# FTDI_only.net
KiCad netlist of a schematic drawn in EAGLE
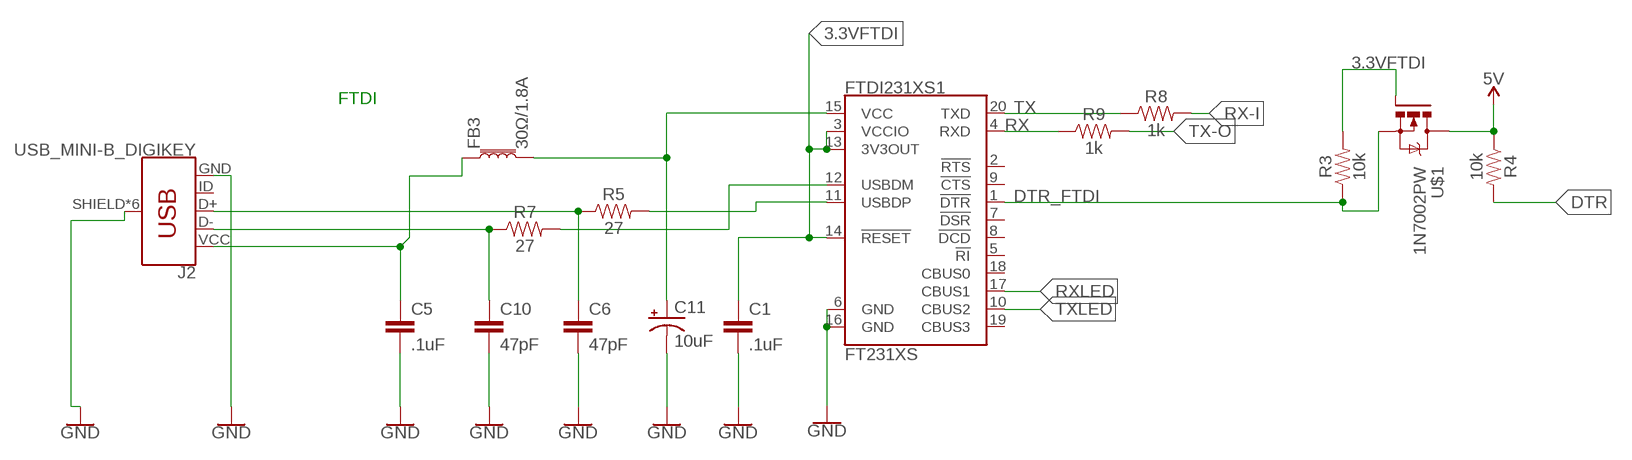
[diagram p0: schematic, sheet 1]

(export (version "E")
  (design (tool "Eeschema 10.0.6"))
  (components
    (comp (ref "C1")
      (value ".1uF")
      (footprint "eagle-import:0402-CAP")
      (libsource (lib "eagle-import") (part ".22UF-CER"))
    )
    (comp (ref "C5")
      (value ".1uF")
      (footprint "eagle-import:0402-CAP")
      (libsource (lib "eagle-import") (part ".22UF-CER"))
    )
    (comp (ref "C6")
      (value "47pF")
      (footprint "eagle-import:0402-CAP")
      (libsource (lib "eagle-import") (part ".22UF-CER"))
    )
    (comp (ref "C10")
      (value "47pF")
      (footprint "eagle-import:0402-CAP")
      (libsource (lib "eagle-import") (part ".22UF-CER"))
    )
    (comp (ref "C11")
      (value "10uF")
      (footprint "eagle-import:EIA3216")
      (libsource (lib "eagle-import") (part "10UF-TANT"))
    )
    (comp (ref "FB3")
      (value "30Ω/1.8A")
      (footprint "eagle-import:0603")
      (libsource (lib "eagle-import") (part "FERRITE_BEAD-0603"))
    )
    (comp (ref "FTDI231XS1")
      (value "FT231XS")
      (footprint "eagle-import:SSOP20_L")
      (libsource (lib "eagle-import") (part "FT231XS"))
    )
    (comp (ref "J2")
      (value "USB_MINI-B_DIGIKEY")
      (footprint "eagle-import:MICRO-USB-DIGIKEY-FCI2")
      (libsource (lib "eagle-import") (part "USB_MINI-B_DIGIKEY"))
    )
    (comp (ref "R3")
      (value "10k")
      (footprint "eagle-import:0603")
      (libsource (lib "eagle-import") (part "0.05OHM-0603-1/5W-1%"))
    )
    (comp (ref "R4")
      (value "10k")
      (footprint "eagle-import:0603")
      (libsource (lib "eagle-import") (part "0.05OHM-0603-1/5W-1%"))
    )
    (comp (ref "R5")
      (value "27")
      (footprint "eagle-import:0603")
      (libsource (lib "eagle-import") (part "0.05OHM-0603-1/5W-1%"))
    )
    (comp (ref "R7")
      (value "27")
      (footprint "eagle-import:0603")
      (libsource (lib "eagle-import") (part "0.05OHM-0603-1/5W-1%"))
    )
    (comp (ref "R8")
      (value "1k")
      (footprint "eagle-import:0603")
      (libsource (lib "eagle-import") (part "0.05OHM-0603-1/5W-1%"))
    )
    (comp (ref "R9")
      (value "1k")
      (footprint "eagle-import:0603")
      (libsource (lib "eagle-import") (part "0.05OHM-0603-1/5W-1%"))
    )
    (comp (ref "U$1")
      (value "1N7002PW")
      (footprint "eagle-import:SOT323W_INFINEON")
      (libsource (lib "eagle-import") (part "1N7002PW"))
    )
  )
  (nets
    (net (code "1") (name "/DTR_FTDI") (class "Default")
      (node (ref "FTDI231XS1") (pin "1") (pinfunction "~{DTR}_1") (pintype "bidirectional"))
      (node (ref "R3") (pin "1") (pinfunction "1_1") (pintype "passive"))
      (node (ref "U$1") (pin "2") (pinfunction "S_2") (pintype "passive"))
    )
    (net (code "2") (name "/RX") (class "Default")
      (node (ref "FTDI231XS1") (pin "4") (pinfunction "RXD_4") (pintype "bidirectional"))
      (node (ref "R9") (pin "1") (pinfunction "1_1") (pintype "passive"))
    )
    (net (code "3") (name "/TX") (class "Default")
      (node (ref "FTDI231XS1") (pin "20") (pinfunction "TXD_20") (pintype "bidirectional"))
      (node (ref "R8") (pin "1") (pinfunction "1_1") (pintype "passive"))
    )
    (net (code "4") (name "/VUSB") (class "Default")
      (node (ref "C11") (pin "A") (pinfunction "+_A") (pintype "passive"))
      (node (ref "C5") (pin "1") (pinfunction "1_1") (pintype "passive"))
      (node (ref "FB3") (pin "1") (pinfunction "1_1") (pintype "passive"))
      (node (ref "FB3") (pin "2") (pinfunction "2_2") (pintype "passive"))
      (node (ref "FTDI231XS1") (pin "15") (pinfunction "VCC_15") (pintype "bidirectional"))
      (node (ref "J2") (pin "VCC") (pinfunction "VBUS_VCC") (pintype "power_in"))
    )
    (net (code "5") (name "3.3VFTDI") (class "Default")
      (node (ref "C1") (pin "1") (pinfunction "1_1") (pintype "passive"))
      (node (ref "FTDI231XS1") (pin "13") (pinfunction "3V3OUT_13") (pintype "bidirectional"))
      (node (ref "FTDI231XS1") (pin "14") (pinfunction "~{RESET}_14") (pintype "bidirectional"))
      (node (ref "FTDI231XS1") (pin "3") (pinfunction "VCCIO_3") (pintype "bidirectional"))
      (node (ref "R3") (pin "2") (pinfunction "2_2") (pintype "passive"))
      (node (ref "U$1") (pin "1") (pinfunction "G_1") (pintype "passive"))
    )
    (net (code "6") (name "5V") (class "Default")
      (node (ref "R4") (pin "1") (pinfunction "1_1") (pintype "passive"))
      (node (ref "U$1") (pin "3") (pinfunction "D_3") (pintype "passive"))
    )
    (net (code "7") (name "DTR") (class "Default")
      (node (ref "R4") (pin "2") (pinfunction "2_2") (pintype "passive"))
    )
    (net (code "8") (name "GND") (class "Default")
      (node (ref "C1") (pin "2") (pinfunction "2_2") (pintype "passive"))
      (node (ref "C10") (pin "2") (pinfunction "2_2") (pintype "passive"))
      (node (ref "C11") (pin "C") (pinfunction "-_C") (pintype "passive"))
      (node (ref "C5") (pin "2") (pinfunction "2_2") (pintype "passive"))
      (node (ref "C6") (pin "2") (pinfunction "2_2") (pintype "passive"))
      (node (ref "FTDI231XS1") (pin "16") (pinfunction "GND_16") (pintype "bidirectional"))
      (node (ref "FTDI231XS1") (pin "6") (pinfunction "GND_6") (pintype "bidirectional"))
      (node (ref "J2") (pin "GND") (pinfunction "GND_GND") (pintype "power_in"))
      (node (ref "J2") (pin "SHIELD") (pinfunction "SHIELD_SHIELD") (pintype "bidirectional"))
      (node (ref "J2") (pin "SHIELD1") (pinfunction "SHIELD_SHIELD1") (pintype "bidirectional"))
      (node (ref "J2") (pin "SHIELD2") (pinfunction "SHIELD_SHIELD2") (pintype "bidirectional"))
      (node (ref "J2") (pin "SHIELD3") (pinfunction "SHIELD_SHIELD3") (pintype "bidirectional"))
      (node (ref "J2") (pin "SHIELD4") (pinfunction "SHIELD_SHIELD4") (pintype "bidirectional"))
      (node (ref "J2") (pin "SHIELD5") (pinfunction "SHIELD_SHIELD5") (pintype "bidirectional"))
    )
    (net (code "9") (name "Net-(C6-Pad1)") (class "Default")
      (node (ref "C6") (pin "1") (pinfunction "1_1") (pintype "passive"))
      (node (ref "J2") (pin "D+") (pinfunction "D+_D+") (pintype "bidirectional"))
      (node (ref "R5") (pin "1") (pinfunction "1_1") (pintype "passive"))
    )
    (net (code "10") (name "Net-(C10-Pad1)") (class "Default")
      (node (ref "C10") (pin "1") (pinfunction "1_1") (pintype "passive"))
      (node (ref "J2") (pin "D-") (pinfunction "D-_D-") (pintype "bidirectional"))
      (node (ref "R7") (pin "1") (pinfunction "1_1") (pintype "passive"))
    )
    (net (code "11") (name "Net-(FTDI231XS1-USBDM)") (class "Default")
      (node (ref "FTDI231XS1") (pin "12") (pinfunction "USBDM_12") (pintype "bidirectional"))
      (node (ref "R7") (pin "2") (pinfunction "2_2") (pintype "passive"))
    )
    (net (code "12") (name "Net-(FTDI231XS1-USBDP)") (class "Default")
      (node (ref "FTDI231XS1") (pin "11") (pinfunction "USBDP_11") (pintype "bidirectional"))
      (node (ref "R5") (pin "2") (pinfunction "2_2") (pintype "passive"))
    )
    (net (code "13") (name "RX-I") (class "Default")
      (node (ref "R8") (pin "2") (pinfunction "2_2") (pintype "passive"))
    )
    (net (code "14") (name "RXLED") (class "Default")
      (node (ref "FTDI231XS1") (pin "17") (pinfunction "CBUS1_17") (pintype "bidirectional"))
    )
    (net (code "15") (name "TX-O") (class "Default")
      (node (ref "R9") (pin "2") (pinfunction "2_2") (pintype "passive"))
    )
    (net (code "16") (name "TXLED") (class "Default")
      (node (ref "FTDI231XS1") (pin "10") (pinfunction "CBUS2_10") (pintype "bidirectional"))
    )
    (net (code "17") (name "unconnected-(FTDI231XS1-CBUS0-Pad18)") (class "Default")
      (node (ref "FTDI231XS1") (pin "18") (pinfunction "CBUS0_18") (pintype "bidirectional"))
    )
    (net (code "18") (name "unconnected-(FTDI231XS1-CBUS3-Pad19)") (class "Default")
      (node (ref "FTDI231XS1") (pin "19") (pinfunction "CBUS3_19") (pintype "bidirectional"))
    )
    (net (code "19") (name "unconnected-(FTDI231XS1-~{CTS}-Pad9)") (class "Default")
      (node (ref "FTDI231XS1") (pin "9") (pinfunction "~{CTS}_9") (pintype "bidirectional"))
    )
    (net (code "20") (name "unconnected-(FTDI231XS1-~{DCD}-Pad8)") (class "Default")
      (node (ref "FTDI231XS1") (pin "8") (pinfunction "~{DCD}_8") (pintype "bidirectional"))
    )
    (net (code "21") (name "unconnected-(FTDI231XS1-~{DSR}-Pad7)") (class "Default")
      (node (ref "FTDI231XS1") (pin "7") (pinfunction "~{DSR}_7") (pintype "bidirectional"))
    )
    (net (code "22") (name "unconnected-(FTDI231XS1-~{RI}-Pad5)") (class "Default")
      (node (ref "FTDI231XS1") (pin "5") (pinfunction "~{RI}_5") (pintype "bidirectional"))
    )
    (net (code "23") (name "unconnected-(FTDI231XS1-~{RTS}-Pad2)") (class "Default")
      (node (ref "FTDI231XS1") (pin "2") (pinfunction "~{RTS}_2") (pintype "bidirectional"))
    )
    (net (code "24") (name "unconnected-(J2-PadID)") (class "Default")
      (node (ref "J2") (pin "ID") (pinfunction "ID_ID") (pintype "bidirectional"))
    )
  )
)
